# DC_Sensor_ESP8266_ADC_NC_02.net
KiCad netlist of a schematic drawn in EAGLE
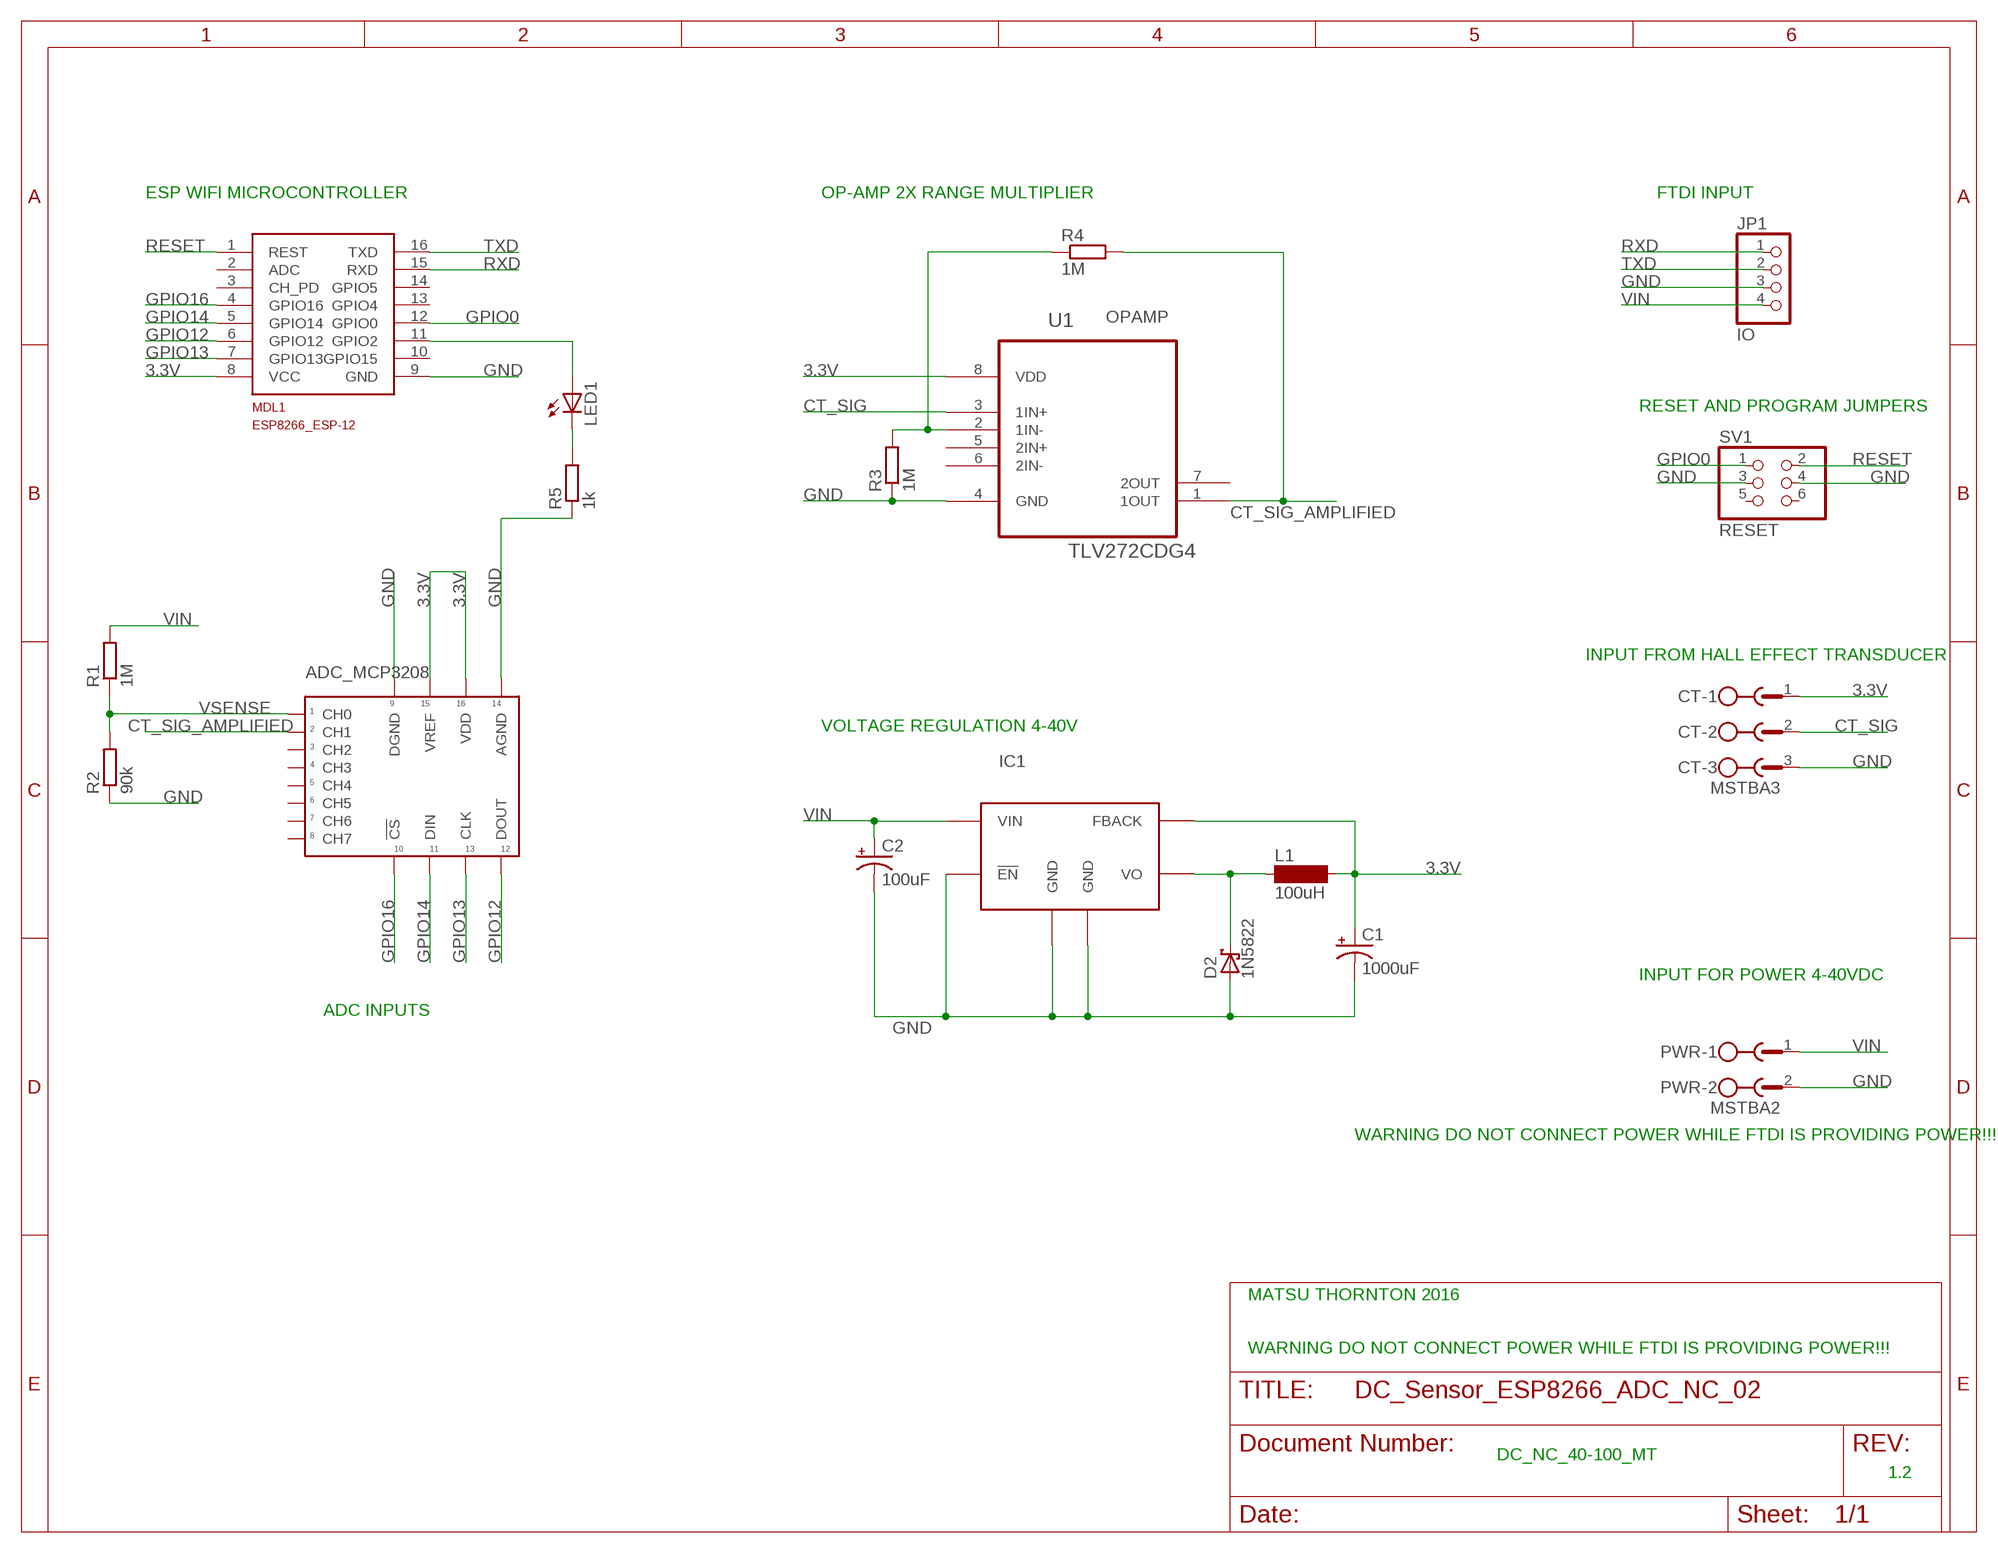
[diagram p0: schematic, sheet 1]

(export (version "E")
  (design (tool "Eeschema 10.0.6"))
  (components
    (comp (ref "ADC_MCP3208")
      (value "21298ESMD")
      (footprint "eagle-import:PDIP16")
      (libsource (lib "eagle-import") (part "21298ESMD"))
    )
    (comp (ref "C1")
      (value "1000uF")
      (footprint "eagle-import:PANASONIC_F")
      (libsource (lib "eagle-import") (part "CPOL-USF"))
    )
    (comp (ref "C2")
      (value "100uF")
      (footprint "eagle-import:PANASONIC_F")
      (libsource (lib "eagle-import") (part "CPOL-USF"))
    )
    (comp (ref "CT")
      (value "MSTBA3")
      (footprint "eagle-import:MSTBA3")
      (fields (field (name "MF") "FARNELL") (field (name "MPN") "1757255"))
      (libsource (lib "eagle-import") (part "MSTBA3"))
    )
    (comp (ref "D2")
      (value "1N5822")
      (footprint "eagle-import:C4111-15")
      (libsource (lib "eagle-import") (part "SCHOTTKY-DIODEC4111-15"))
    )
    (comp (ref "IC1")
      (value "LM2576S")
      (footprint "eagle-import:TO263-5")
      (libsource (lib "eagle-import") (part "LM2576S"))
    )
    (comp (ref "JP1")
      (value "IO")
      (footprint "eagle-import:1X04")
      (libsource (lib "eagle-import") (part "PINHD-1X4"))
    )
    (comp (ref "L1")
      (value "100uH")
      (footprint "eagle-import:BS11")
      (libsource (lib "eagle-import") (part "BS11"))
    )
    (comp (ref "LED1")
      (value "LEDCHIP-LED0603")
      (footprint "eagle-import:CHIP-LED0603")
      (libsource (lib "eagle-import") (part "LEDCHIP-LED0603"))
    )
    (comp (ref "MDL1")
      (value "ESP8266-12GPIO04/05_CORRECTED")
      (footprint "eagle-import:ESP8266-ESP12")
      (libsource (lib "eagle-import") (part "ESP8266-12GPIO04/05_CORRECTED"))
    )
    (comp (ref "PWR")
      (value "MSTBA2")
      (footprint "eagle-import:MSTBA2")
      (fields (field (name "MF") "FARNELL") (field (name "MPN") "1757242"))
      (libsource (lib "eagle-import") (part "MSTBA2"))
    )
    (comp (ref "R1")
      (value "1M")
      (footprint "eagle-import:R0805")
      (libsource (lib "eagle-import") (part "R-EU_R0805"))
    )
    (comp (ref "R2")
      (value "90k")
      (footprint "eagle-import:R0805")
      (libsource (lib "eagle-import") (part "R-EU_R0805"))
    )
    (comp (ref "R3")
      (value "1M")
      (footprint "eagle-import:R0805")
      (libsource (lib "eagle-import") (part "R-EU_R0805"))
    )
    (comp (ref "R4")
      (value "1M")
      (footprint "eagle-import:R0805")
      (libsource (lib "eagle-import") (part "R-EU_R0805"))
    )
    (comp (ref "R5")
      (value "1k")
      (footprint "eagle-import:R0805")
      (libsource (lib "eagle-import") (part "R-EU_R0805"))
    )
    (comp (ref "SV1")
      (value "RESET")
      (footprint "eagle-import:2X03")
      (libsource (lib "eagle-import") (part "PINHD-2X3"))
    )
    (comp (ref "U1")
      (value "TLV272CDG4")
      (footprint "eagle-import:SOIC127P600X175-8N")
      (fields (field (name "TYPE") "OPAMP"))
      (libsource (lib "eagle-import") (part "TLV272CDG4"))
    )
  )
  (nets
    (net (code "1") (name "/3.3V") (class "Default")
      (node (ref "ADC_MCP3208") (pin "P$15") (pinfunction "VREF_P$15") (pintype "bidirectional"))
      (node (ref "ADC_MCP3208") (pin "P$16") (pinfunction "VDD_P$16") (pintype "bidirectional"))
      (node (ref "C1") (pin "+") (pinfunction "+_+") (pintype "passive"))
      (node (ref "CT") (pin "1") (pinfunction "1_1") (pintype "passive"))
      (node (ref "IC1") (pin "4") (pinfunction "FBACK_4") (pintype "bidirectional"))
      (node (ref "L1") (pin "2") (pinfunction "2_2") (pintype "passive"))
      (node (ref "MDL1") (pin "8") (pinfunction "VCC_8") (pintype "bidirectional"))
      (node (ref "U1") (pin "8") (pinfunction "VDD_8") (pintype "power_in"))
    )
    (net (code "2") (name "/CT_SIG") (class "Default")
      (node (ref "CT") (pin "2") (pinfunction "1_2") (pintype "passive"))
      (node (ref "U1") (pin "3") (pinfunction "1IN+_3") (pintype "input"))
    )
    (net (code "3") (name "/CT_SIG_AMPLIFIED") (class "Default")
      (node (ref "ADC_MCP3208") (pin "P$2") (pinfunction "CH1_P$2") (pintype "bidirectional"))
      (node (ref "R4") (pin "2") (pinfunction "2_2") (pintype "passive"))
      (node (ref "U1") (pin "1") (pinfunction "1OUT_1") (pintype "output"))
    )
    (net (code "4") (name "/GND") (class "Default")
      (node (ref "ADC_MCP3208") (pin "P$14") (pinfunction "AGND_P$14") (pintype "bidirectional"))
      (node (ref "ADC_MCP3208") (pin "P$9") (pinfunction "DGND_P$9") (pintype "bidirectional"))
      (node (ref "C1") (pin "-") (pinfunction "-_-") (pintype "passive"))
      (node (ref "C2") (pin "-") (pinfunction "-_-") (pintype "passive"))
      (node (ref "CT") (pin "3") (pinfunction "1_3") (pintype "passive"))
      (node (ref "D2") (pin "A") (pinfunction "A_A") (pintype "passive"))
      (node (ref "IC1") (pin "3") (pinfunction "GND_3") (pintype "bidirectional"))
      (node (ref "IC1") (pin "5") (pinfunction "~{EN}_5") (pintype "bidirectional"))
      (node (ref "IC1") (pin "TAB") (pinfunction "GND_TAB") (pintype "bidirectional"))
      (node (ref "JP1") (pin "3") (pinfunction "3_3") (pintype "passive"))
      (node (ref "MDL1") (pin "9") (pinfunction "GND_9") (pintype "bidirectional"))
      (node (ref "PWR") (pin "2") (pinfunction "1_2") (pintype "passive"))
      (node (ref "R2") (pin "1") (pinfunction "1_1") (pintype "passive"))
      (node (ref "R3") (pin "1") (pinfunction "1_1") (pintype "passive"))
      (node (ref "R5") (pin "1") (pinfunction "1_1") (pintype "passive"))
      (node (ref "SV1") (pin "3") (pinfunction "3_3") (pintype "passive"))
      (node (ref "SV1") (pin "4") (pinfunction "4_4") (pintype "passive"))
      (node (ref "U1") (pin "4") (pinfunction "GND_4") (pintype "passive"))
    )
    (net (code "5") (name "/GPIO0") (class "Default")
      (node (ref "MDL1") (pin "12") (pinfunction "GPIO0_12") (pintype "bidirectional"))
      (node (ref "SV1") (pin "1") (pinfunction "1_1") (pintype "passive"))
    )
    (net (code "6") (name "/GPIO12") (class "Default")
      (node (ref "ADC_MCP3208") (pin "P$12") (pinfunction "DOUT_P$12") (pintype "bidirectional"))
      (node (ref "MDL1") (pin "6") (pinfunction "GPIO12_6") (pintype "bidirectional"))
    )
    (net (code "7") (name "/GPIO13") (class "Default")
      (node (ref "ADC_MCP3208") (pin "P$13") (pinfunction "CLK_P$13") (pintype "bidirectional"))
      (node (ref "MDL1") (pin "7") (pinfunction "GPIO13_7") (pintype "bidirectional"))
    )
    (net (code "8") (name "/GPIO14") (class "Default")
      (node (ref "ADC_MCP3208") (pin "P$11") (pinfunction "DIN_P$11") (pintype "bidirectional"))
      (node (ref "MDL1") (pin "5") (pinfunction "GPIO14_5") (pintype "bidirectional"))
    )
    (net (code "9") (name "/GPIO16") (class "Default")
      (node (ref "ADC_MCP3208") (pin "P$10") (pinfunction "~{CS}_P$10") (pintype "bidirectional"))
      (node (ref "MDL1") (pin "4") (pinfunction "GPIO16_4") (pintype "bidirectional"))
    )
    (net (code "10") (name "/RESET") (class "Default")
      (node (ref "MDL1") (pin "1") (pinfunction "REST_1") (pintype "bidirectional"))
      (node (ref "SV1") (pin "2") (pinfunction "2_2") (pintype "passive"))
    )
    (net (code "11") (name "/RXD") (class "Default")
      (node (ref "JP1") (pin "1") (pinfunction "1_1") (pintype "passive"))
      (node (ref "MDL1") (pin "15") (pinfunction "RXD_15") (pintype "bidirectional"))
    )
    (net (code "12") (name "/TXD") (class "Default")
      (node (ref "JP1") (pin "2") (pinfunction "2_2") (pintype "passive"))
      (node (ref "MDL1") (pin "16") (pinfunction "TXD_16") (pintype "bidirectional"))
    )
    (net (code "13") (name "/VIN") (class "Default")
      (node (ref "C2") (pin "+") (pinfunction "+_+") (pintype "passive"))
      (node (ref "IC1") (pin "1") (pinfunction "VIN_1") (pintype "bidirectional"))
      (node (ref "JP1") (pin "4") (pinfunction "4_4") (pintype "passive"))
      (node (ref "PWR") (pin "1") (pinfunction "1_1") (pintype "passive"))
      (node (ref "R1") (pin "2") (pinfunction "2_2") (pintype "passive"))
    )
    (net (code "14") (name "/VSENSE") (class "Default")
      (node (ref "ADC_MCP3208") (pin "P$1") (pinfunction "CH0_P$1") (pintype "bidirectional"))
      (node (ref "R1") (pin "1") (pinfunction "1_1") (pintype "passive"))
      (node (ref "R2") (pin "2") (pinfunction "2_2") (pintype "passive"))
    )
    (net (code "15") (name "Net-(IC1-VO)") (class "Default")
      (node (ref "D2") (pin "C") (pinfunction "C_C") (pintype "passive"))
      (node (ref "IC1") (pin "2") (pinfunction "VO_2") (pintype "bidirectional"))
      (node (ref "L1") (pin "1") (pinfunction "1_1") (pintype "passive"))
    )
    (net (code "16") (name "Net-(LED1-PadC)") (class "Default")
      (node (ref "LED1") (pin "C") (pinfunction "C_C") (pintype "passive"))
      (node (ref "R5") (pin "2") (pinfunction "2_2") (pintype "passive"))
    )
    (net (code "17") (name "Net-(MDL1-GPIO2)") (class "Default")
      (node (ref "LED1") (pin "A") (pinfunction "A_A") (pintype "passive"))
      (node (ref "MDL1") (pin "11") (pinfunction "GPIO2_11") (pintype "bidirectional"))
    )
    (net (code "18") (name "Net-(U1-1IN-)") (class "Default")
      (node (ref "R3") (pin "2") (pinfunction "2_2") (pintype "passive"))
      (node (ref "R4") (pin "1") (pinfunction "1_1") (pintype "passive"))
      (node (ref "U1") (pin "2") (pinfunction "1IN-_2") (pintype "input"))
    )
    (net (code "19") (name "unconnected-(ADC_MCP3208-CH2-PadP$3)") (class "Default")
      (node (ref "ADC_MCP3208") (pin "P$3") (pinfunction "CH2_P$3") (pintype "bidirectional"))
    )
    (net (code "20") (name "unconnected-(ADC_MCP3208-CH3-PadP$4)") (class "Default")
      (node (ref "ADC_MCP3208") (pin "P$4") (pinfunction "CH3_P$4") (pintype "bidirectional"))
    )
    (net (code "21") (name "unconnected-(ADC_MCP3208-CH4-PadP$5)") (class "Default")
      (node (ref "ADC_MCP3208") (pin "P$5") (pinfunction "CH4_P$5") (pintype "bidirectional"))
    )
    (net (code "22") (name "unconnected-(ADC_MCP3208-CH5-PadP$6)") (class "Default")
      (node (ref "ADC_MCP3208") (pin "P$6") (pinfunction "CH5_P$6") (pintype "bidirectional"))
    )
    (net (code "23") (name "unconnected-(ADC_MCP3208-CH6-PadP$7)") (class "Default")
      (node (ref "ADC_MCP3208") (pin "P$7") (pinfunction "CH6_P$7") (pintype "bidirectional"))
    )
    (net (code "24") (name "unconnected-(ADC_MCP3208-CH7-PadP$8)") (class "Default")
      (node (ref "ADC_MCP3208") (pin "P$8") (pinfunction "CH7_P$8") (pintype "bidirectional"))
    )
    (net (code "25") (name "unconnected-(MDL1-ADC-Pad2)") (class "Default")
      (node (ref "MDL1") (pin "2") (pinfunction "ADC_2") (pintype "bidirectional"))
    )
    (net (code "26") (name "unconnected-(MDL1-CH_PD-Pad3)") (class "Default")
      (node (ref "MDL1") (pin "3") (pinfunction "CH_PD_3") (pintype "bidirectional"))
    )
    (net (code "27") (name "unconnected-(MDL1-GPIO4-Pad13)") (class "Default")
      (node (ref "MDL1") (pin "13") (pinfunction "GPIO4_13") (pintype "bidirectional"))
    )
    (net (code "28") (name "unconnected-(MDL1-GPIO5-Pad14)") (class "Default")
      (node (ref "MDL1") (pin "14") (pinfunction "GPIO5_14") (pintype "bidirectional"))
    )
    (net (code "29") (name "unconnected-(MDL1-GPIO15-Pad10)") (class "Default")
      (node (ref "MDL1") (pin "10") (pinfunction "GPIO15_10") (pintype "bidirectional"))
    )
    (net (code "30") (name "unconnected-(SV1-Pad5)") (class "Default")
      (node (ref "SV1") (pin "5") (pinfunction "5_5") (pintype "passive"))
    )
    (net (code "31") (name "unconnected-(SV1-Pad6)") (class "Default")
      (node (ref "SV1") (pin "6") (pinfunction "6_6") (pintype "passive"))
    )
    (net (code "32") (name "unconnected-(U1-2IN+-Pad5)") (class "Default")
      (node (ref "U1") (pin "5") (pinfunction "2IN+_5") (pintype "input"))
    )
    (net (code "33") (name "unconnected-(U1-2IN--Pad6)") (class "Default")
      (node (ref "U1") (pin "6") (pinfunction "2IN-_6") (pintype "input"))
    )
    (net (code "34") (name "unconnected-(U1-2OUT-Pad7)") (class "Default")
      (node (ref "U1") (pin "7") (pinfunction "2OUT_7") (pintype "output"))
    )
  )
)
